# CPU_SDIO_UART_I2C_I2C.net
KiCad netlist of a schematic drawn in Altium Designer
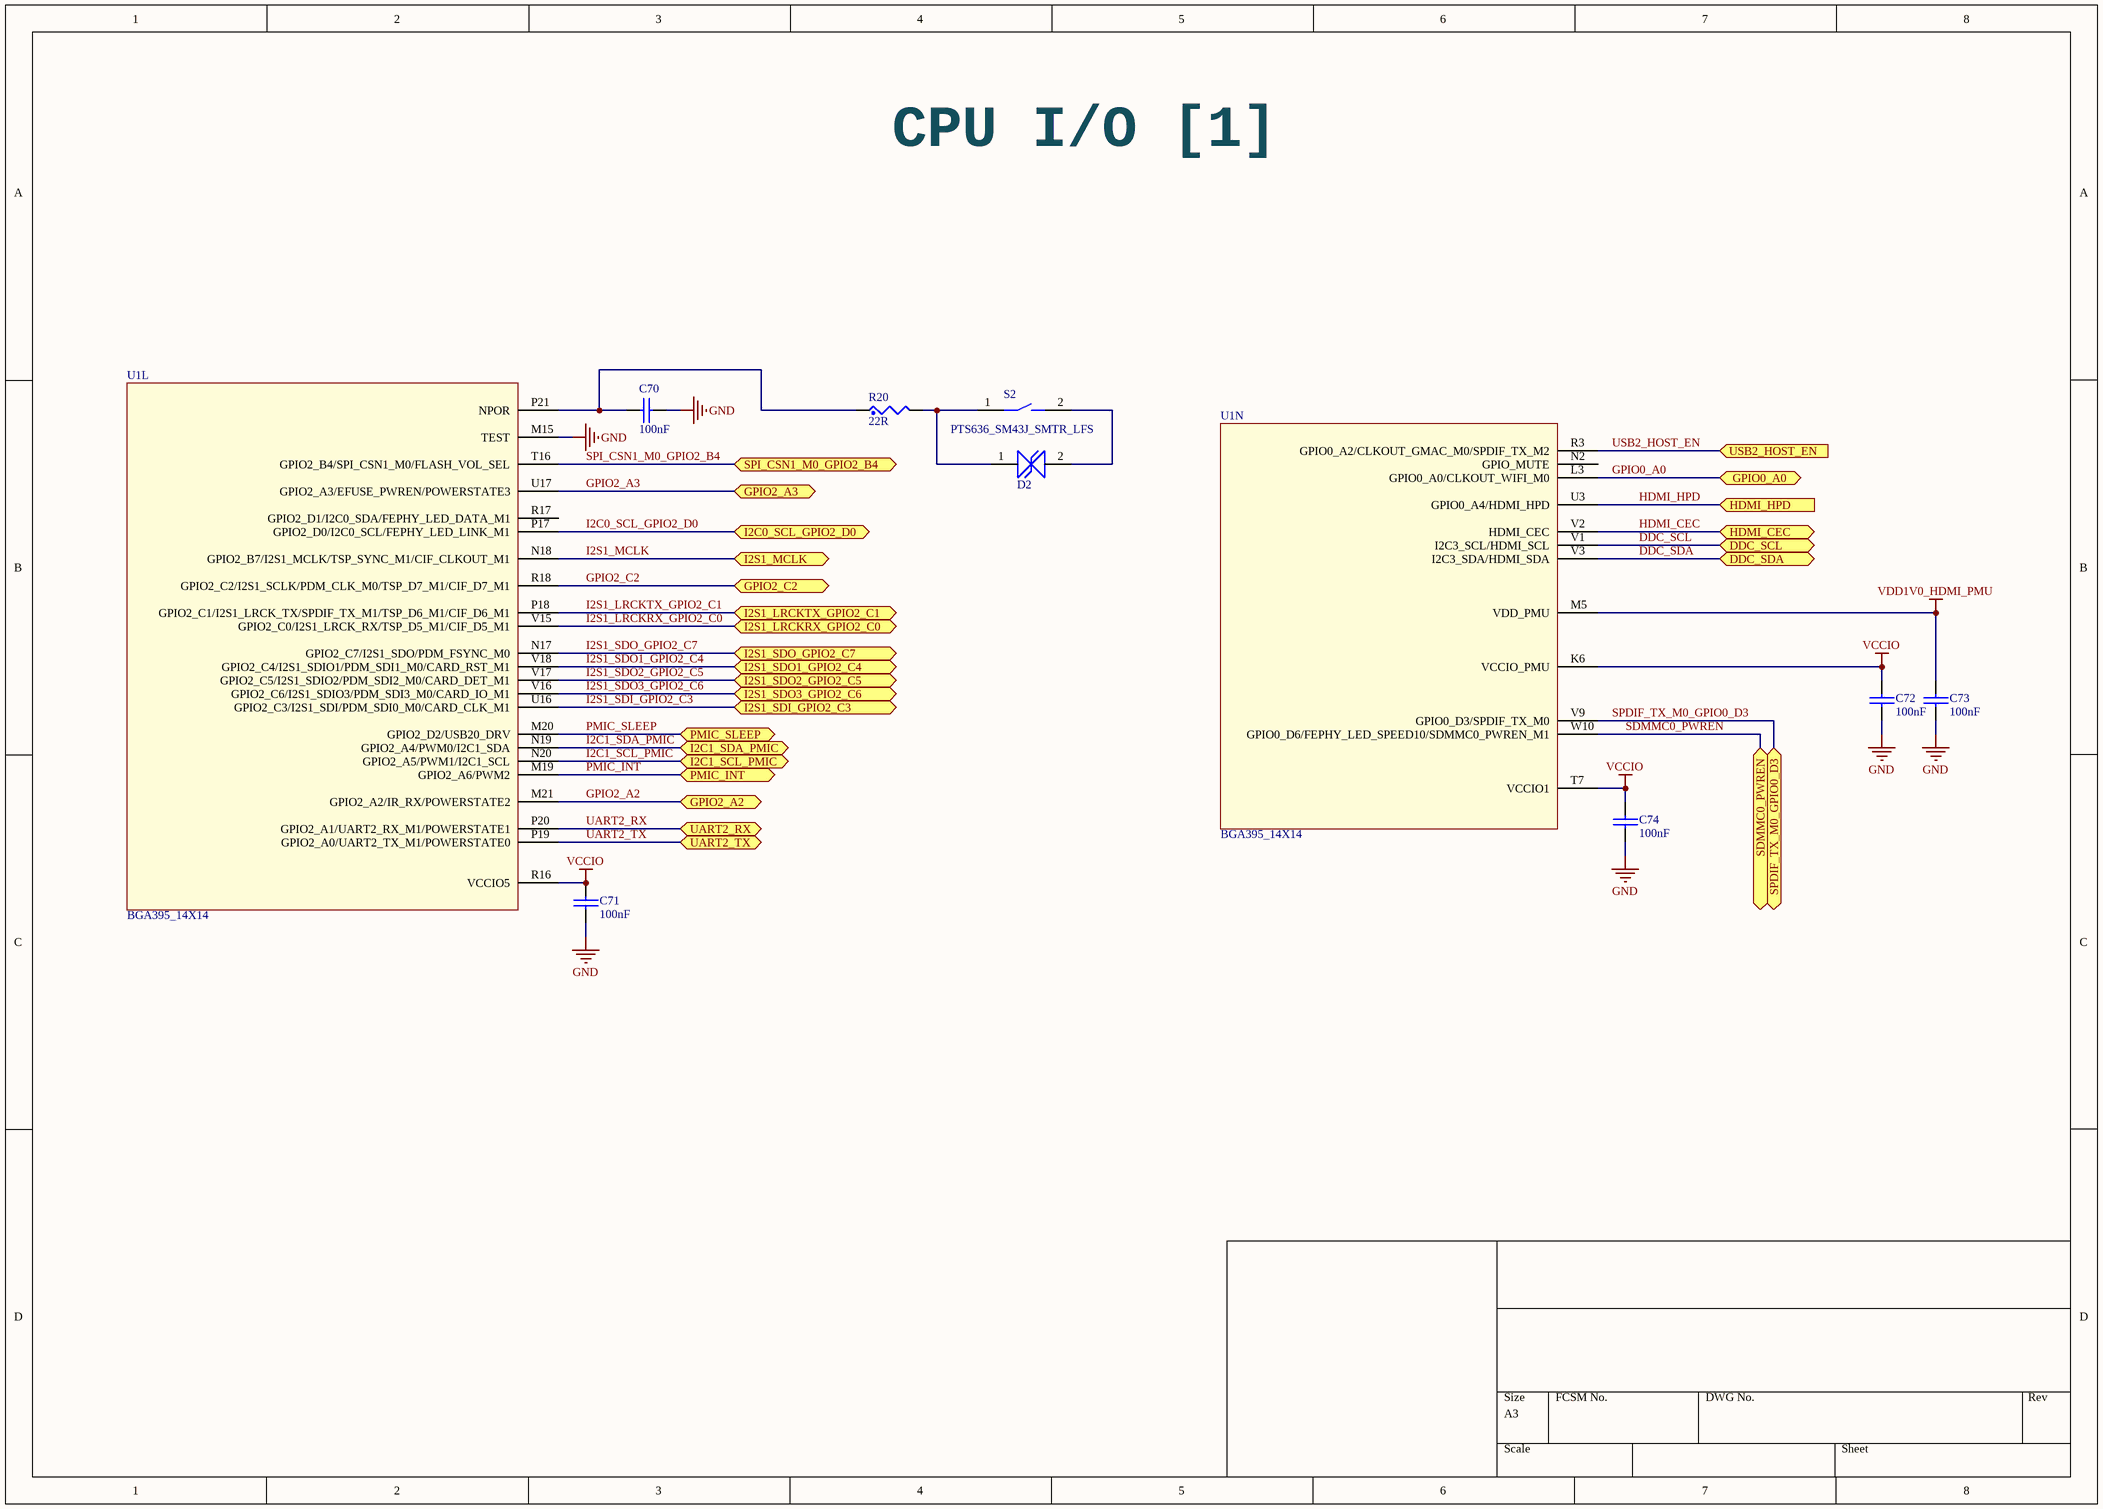
[diagram p0: CPU_SDIO_UART_I2C_I2C.SchDoc]

(export (version "E")
  (design (tool "Eeschema 10.0.6"))
  (components
    (comp (ref "C70")
      (value "100nF")
      (footprint "0402_CC - C")
      (libsource (lib "AAR_RockChip_RK3328") (part "CAP_NP"))
    )
    (comp (ref "C71")
      (value "100nF")
      (footprint "0402_CC - C")
      (libsource (lib "AAR_RockChip_RK3328") (part "CAP_NP"))
    )
    (comp (ref "C72")
      (value "100nF")
      (footprint "0402_CC - C")
      (libsource (lib "AAR_RockChip_RK3328") (part "CAP_NP"))
    )
    (comp (ref "C73")
      (value "100nF")
      (footprint "0402_CC - C")
      (libsource (lib "AAR_RockChip_RK3328") (part "CAP_NP"))
    )
    (comp (ref "C74")
      (value "100nF")
      (footprint "0402_CC - C")
      (libsource (lib "AAR_RockChip_RK3328") (part "CAP_NP"))
    )
    (comp (ref "D2")
      (value "TVS")
      (footprint "SODFL100X45-2N")
      (fields (field (name "MFR_PART_NO") "ESD5451N-2/TR") (field (name "LCSC PART #") "C239604"))
      (libsource (lib "AAR_RockChip_RK3328") (part "ESD5451N"))
    )
    (comp (ref "R20")
      (value "22R")
      (footprint "0402_CR")
      (libsource (lib "AAR_RockChip_RK3328") (part "RES"))
    )
    (comp (ref "S2")
      (value "PTS636_SM43J_SMTR_LFS")
      (footprint "PTS636_3.5_6_4.3")
      (description "Tactile Switches Tact 50mA 12VDC, 6.0x3.5, 4.3mm H, 180gf, J leads, No ground pin, Black Actuator")
      (fields (field (name "MFR_PART_NO") "PTS636 SM43J SMTR LFS"))
      (libsource (lib "AAR_RockChip_RK3328") (part "PTS636"))
    )
    (comp (ref "U1")
      (value "BGA395_14X14")
      (footprint "BGA395C65P21X21_1750X1750X117")
      (description "By AAR")
      (libsource (lib "AAR_RockChip_RK3328") (part "RK3328"))
    )
  )
  (nets
    (net (code "1") (name "/DDC_SCL") (class "Default")
      (node (ref "U1") (pin "V1") (pinfunction "I2C3_SCL/HDMI_SCL_V1") (pintype "passive"))
    )
    (net (code "2") (name "/DDC_SDA") (class "Default")
      (node (ref "U1") (pin "V3") (pinfunction "I2C3_SDA/HDMI_SDA_V3") (pintype "passive"))
    )
    (net (code "3") (name "/GPIO0_A0") (class "Default")
      (node (ref "U1") (pin "L3") (pinfunction "GPIO0_A0/CLKOUT_WIFI_M0_L3") (pintype "passive"))
    )
    (net (code "4") (name "/GPIO2_A2") (class "Default")
      (node (ref "U1") (pin "M21") (pinfunction "GPIO2_A2/IR_RX/POWERSTATE2_M21") (pintype "passive"))
    )
    (net (code "5") (name "/GPIO2_A3") (class "Default")
      (node (ref "U1") (pin "U17") (pinfunction "GPIO2_A3/EFUSE_PWREN/POWERSTATE3_U17") (pintype "passive"))
    )
    (net (code "6") (name "/GPIO2_C2") (class "Default")
      (node (ref "U1") (pin "R18") (pinfunction "GPIO2_C2/I2S1_SCLK/PDM_CLK_M0/TSP_D7_M1/CIF_D7_M1_R18") (pintype "passive"))
    )
    (net (code "7") (name "/HDMI_CEC") (class "Default")
      (node (ref "U1") (pin "V2") (pinfunction "HDMI_CEC_V2") (pintype "passive"))
    )
    (net (code "8") (name "/HDMI_HPD") (class "Default")
      (node (ref "U1") (pin "U3") (pinfunction "GPIO0_A4/HDMI_HPD_U3") (pintype "passive"))
    )
    (net (code "9") (name "/I2C0_SCL_GPIO2_D0") (class "Default")
      (node (ref "U1") (pin "P17") (pinfunction "GPIO2_D0/I2C0_SCL/FEPHY_LED_LINK_M1_P17") (pintype "passive"))
    )
    (net (code "10") (name "/I2C1_SCL_PMIC") (class "Default")
      (node (ref "U1") (pin "N20") (pinfunction "GPIO2_A5/PWM1/I2C1_SCL_N20") (pintype "passive"))
    )
    (net (code "11") (name "/I2C1_SDA_PMIC") (class "Default")
      (node (ref "U1") (pin "N19") (pinfunction "GPIO2_A4/PWM0/I2C1_SDA_N19") (pintype "passive"))
    )
    (net (code "12") (name "/I2S1_LRCKRX_GPIO2_C0") (class "Default")
      (node (ref "U1") (pin "V15") (pinfunction "GPIO2_C0/I2S1_LRCK_RX/TSP_D5_M1/CIF_D5_M1_V15") (pintype "passive"))
    )
    (net (code "13") (name "/I2S1_LRCKTX_GPIO2_C1") (class "Default")
      (node (ref "U1") (pin "P18") (pinfunction "GPIO2_C1/I2S1_LRCK_TX/SPDIF_TX_M1/TSP_D6_M1/CIF_D6_M1_P18") (pintype "passive"))
    )
    (net (code "14") (name "/I2S1_MCLK") (class "Default")
      (node (ref "U1") (pin "N18") (pinfunction "GPIO2_B7/I2S1_MCLK/TSP_SYNC_M1/CIF_CLKOUT_M1_N18") (pintype "passive"))
    )
    (net (code "15") (name "/I2S1_SDI_GPIO2_C3") (class "Default")
      (node (ref "U1") (pin "U16") (pinfunction "GPIO2_C3/I2S1_SDI/PDM_SDI0_M0/CARD_CLK_M1_U16") (pintype "passive"))
    )
    (net (code "16") (name "/I2S1_SDO1_GPIO2_C4") (class "Default")
      (node (ref "U1") (pin "V18") (pinfunction "GPIO2_C4/I2S1_SDIO1/PDM_SDI1_M0/CARD_RST_M1_V18") (pintype "passive"))
    )
    (net (code "17") (name "/I2S1_SDO2_GPIO2_C5") (class "Default")
      (node (ref "U1") (pin "V17") (pinfunction "GPIO2_C5/I2S1_SDIO2/PDM_SDI2_M0/CARD_DET_M1_V17") (pintype "passive"))
    )
    (net (code "18") (name "/I2S1_SDO3_GPIO2_C6") (class "Default")
      (node (ref "U1") (pin "V16") (pinfunction "GPIO2_C6/I2S1_SDIO3/PDM_SDI3_M0/CARD_IO_M1_V16") (pintype "passive"))
    )
    (net (code "19") (name "/I2S1_SDO_GPIO2_C7") (class "Default")
      (node (ref "U1") (pin "N17") (pinfunction "GPIO2_C7/I2S1_SDO/PDM_FSYNC_M0_N17") (pintype "passive"))
    )
    (net (code "20") (name "/PMIC_INT") (class "Default")
      (node (ref "U1") (pin "M19") (pinfunction "GPIO2_A6/PWM2_M19") (pintype "passive"))
    )
    (net (code "21") (name "/PMIC_SLEEP") (class "Default")
      (node (ref "U1") (pin "M20") (pinfunction "GPIO2_D2/USB20_DRV_M20") (pintype "passive"))
    )
    (net (code "22") (name "/SDMMC0_PWREN") (class "Default")
      (node (ref "U1") (pin "W10") (pinfunction "GPIO0_D6/FEPHY_LED_SPEED10/SDMMC0_PWREN_M1_W10") (pintype "passive"))
    )
    (net (code "23") (name "/SPDIF_TX_M0_GPIO0_D3") (class "Default")
      (node (ref "U1") (pin "V9") (pinfunction "GPIO0_D3/SPDIF_TX_M0_V9") (pintype "passive"))
    )
    (net (code "24") (name "/SPI_CSN1_M0_GPIO2_B4") (class "Default")
      (node (ref "U1") (pin "T16") (pinfunction "GPIO2_B4/SPI_CSN1_M0/FLASH_VOL_SEL_T16") (pintype "passive"))
    )
    (net (code "25") (name "/UART2_RX") (class "Default")
      (node (ref "U1") (pin "P20") (pinfunction "GPIO2_A1/UART2_RX_M1/POWERSTATE1_P20") (pintype "passive"))
    )
    (net (code "26") (name "/UART2_TX") (class "Default")
      (node (ref "U1") (pin "P19") (pinfunction "GPIO2_A0/UART2_TX_M1/POWERSTATE0_P19") (pintype "passive"))
    )
    (net (code "27") (name "/USB2_HOST_EN") (class "Default")
      (node (ref "U1") (pin "R3") (pinfunction "GPIO0_A2/CLKOUT_GMAC_M0/SPDIF_TX_M2_R3") (pintype "passive"))
    )
    (net (code "28") (name "GND") (class "Default")
      (node (ref "C70") (pin "2") (pinfunction "2_2") (pintype "passive"))
      (node (ref "C71") (pin "1") (pinfunction "1_1") (pintype "passive"))
      (node (ref "C72") (pin "1") (pinfunction "1_1") (pintype "passive"))
      (node (ref "C73") (pin "1") (pinfunction "1_1") (pintype "passive"))
      (node (ref "C74") (pin "1") (pinfunction "1_1") (pintype "passive"))
      (node (ref "U1") (pin "M15") (pinfunction "TEST_M15") (pintype "passive"))
    )
    (net (code "29") (name "Net-(D2-Pad1)") (class "Default")
      (node (ref "D2") (pin "1") (pinfunction "1_1") (pintype "passive"))
      (node (ref "R20") (pin "2") (pinfunction "2_2") (pintype "passive"))
      (node (ref "S2") (pin "1") (pinfunction "1_1") (pintype "passive"))
    )
    (net (code "30") (name "Net-(D2-Pad2)") (class "Default")
      (node (ref "D2") (pin "2") (pinfunction "2_2") (pintype "passive"))
      (node (ref "S2") (pin "2") (pinfunction "2_2") (pintype "passive"))
    )
    (net (code "31") (name "Net-(U1L-NPOR)") (class "Default")
      (node (ref "C70") (pin "1") (pinfunction "1_1") (pintype "passive"))
      (node (ref "R20") (pin "1") (pinfunction "1_1") (pintype "passive"))
      (node (ref "U1") (pin "P21") (pinfunction "NPOR_P21") (pintype "passive"))
    )
    (net (code "32") (name "VCCIO") (class "Default")
      (node (ref "C71") (pin "2") (pinfunction "2_2") (pintype "passive"))
      (node (ref "C72") (pin "2") (pinfunction "2_2") (pintype "passive"))
      (node (ref "C74") (pin "2") (pinfunction "2_2") (pintype "passive"))
      (node (ref "U1") (pin "K6") (pinfunction "VCCIO_PMU_K6") (pintype "passive"))
      (node (ref "U1") (pin "R16") (pinfunction "VCCIO5_R16") (pintype "passive"))
      (node (ref "U1") (pin "T7") (pinfunction "VCCIO1_T7") (pintype "passive"))
    )
    (net (code "33") (name "VDD1V0_HDMI_PMU") (class "Default")
      (node (ref "C73") (pin "2") (pinfunction "2_2") (pintype "passive"))
      (node (ref "U1") (pin "M5") (pinfunction "VDD_PMU_M5") (pintype "passive"))
    )
    (net (code "34") (name "unconnected-(U1L-GPIO2_D1{slash}I2C0_SDA{slash}FEPHY_LED_DATA_M1-PadR17)") (class "Default")
      (node (ref "U1") (pin "R17") (pinfunction "GPIO2_D1/I2C0_SDA/FEPHY_LED_DATA_M1_R17") (pintype "passive"))
    )
    (net (code "35") (name "unconnected-(U1N-GPIO_MUTE-PadN2)") (class "Default")
      (node (ref "U1") (pin "N2") (pinfunction "GPIO_MUTE_N2") (pintype "passive"))
    )
  )
)
